# ESP-WROOM-32.net
KiCad netlist of a schematic drawn in Altium Designer
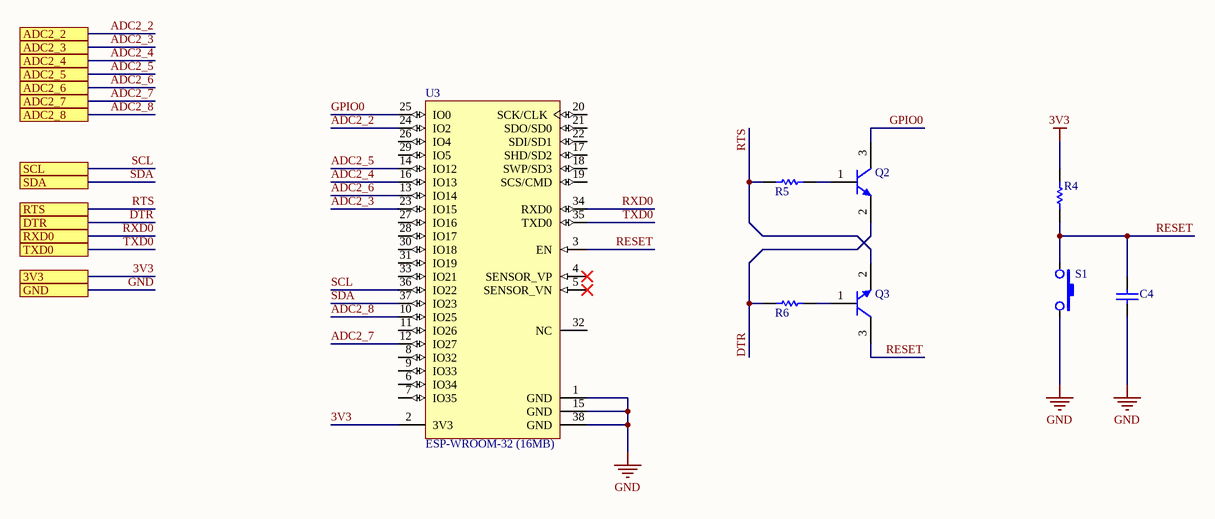
[diagram p0: ESP-WROOM-32.SchDoc]

(export (version "E")
  (design (tool "Eeschema 10.0.6"))
  (components
    (comp (ref "C4")
      (value "C0805C105K4RAC7800")
      (footprint "CAPC2013X145X50NL20T25")
      (description "1µF ±10% 16V Ceramic Capacitor X7R 0805 (2012 Metric)")
      (fields (field (name "MANUFACTURER") "Kemet"))
      (libsource (lib "Altium Content Vault") (part "CAP"))
    )
    (comp (ref "Q2")
      (value "MMBT2222ALT1G")
      (footprint "ONSC-SOT-23-3-318-08_V")
      (description "General Purpose Transistor, NPN Silicon, 3-Pin SOT-23, Pb-Free, Tape and Reel")
      (fields (field (name "MANUFACTURER") "On Semiconductor"))
      (libsource (lib "Altium Content Vault") (part "ONSC-NPN-B1E2C3-3"))
    )
    (comp (ref "Q3")
      (value "MMBT2222ALT1G")
      (footprint "ONSC-SOT-23-3-318-08_V")
      (description "General Purpose Transistor, NPN Silicon, 3-Pin SOT-23, Pb-Free, Tape and Reel")
      (fields (field (name "MANUFACTURER") "On Semiconductor"))
      (libsource (lib "Altium Content Vault") (part "ONSC-NPN-B1E2C3-3"))
    )
    (comp (ref "R4")
      (value "RK73B2ATTD103J")
      (footprint "RESC2013X60X30NL20T20")
      (fields (field (name "MANUFACTURER") "KOA Speer"))
      (libsource (lib "Altium Content Vault") (part "RES"))
    )
    (comp (ref "R5")
      (value "RK73B2ATTD103J")
      (footprint "RESC2013X60X30NL20T20")
      (fields (field (name "MANUFACTURER") "KOA Speer"))
      (libsource (lib "Altium Content Vault") (part "RES"))
    )
    (comp (ref "R6")
      (value "RK73B2ATTD103J")
      (footprint "RESC2013X60X30NL20T20")
      (fields (field (name "MANUFACTURER") "KOA Speer"))
      (libsource (lib "Altium Content Vault") (part "RES"))
    )
    (comp (ref "S1")
      (value "PTS820J25MSMTRLFS")
      (footprint "SMT_SW_PTS_820")
      (description "Tactile Switch SPST-NO Top Actuated Surface Moun")
      (libsource (lib "LIB_FIT") (part "PTS820J25MSMTRLFS"))
    )
    (comp (ref "U3")
      (value "ESP-WROOM-32 (16MB)")
      (footprint "OLMX-ESP-WROOM-32")
      (description "Espressif System, 2.7 to 3.6 V, -40 to 85 degC, 38-Pin SMD")
      (libsource (lib "Altium Content Vault") (part "OLMX-ESP-WROOM-32-38"))
    )
  )
  (nets
    (net (code "1") (name "/ADC2_2") (class "Default")
      (node (ref "U3") (pin "24") (pinfunction "IO2_24") (pintype "bidirectional"))
    )
    (net (code "2") (name "/ADC2_3") (class "Default")
      (node (ref "U3") (pin "23") (pinfunction "IO15_23") (pintype "bidirectional"))
    )
    (net (code "3") (name "/ADC2_4") (class "Default")
      (node (ref "U3") (pin "16") (pinfunction "IO13_16") (pintype "bidirectional"))
    )
    (net (code "4") (name "/ADC2_5") (class "Default")
      (node (ref "U3") (pin "14") (pinfunction "IO12_14") (pintype "bidirectional"))
    )
    (net (code "5") (name "/ADC2_6") (class "Default")
      (node (ref "U3") (pin "13") (pinfunction "IO14_13") (pintype "bidirectional"))
    )
    (net (code "6") (name "/ADC2_7") (class "Default")
      (node (ref "U3") (pin "12") (pinfunction "IO27_12") (pintype "bidirectional"))
    )
    (net (code "7") (name "/ADC2_8") (class "Default")
      (node (ref "U3") (pin "10") (pinfunction "IO25_10") (pintype "bidirectional"))
    )
    (net (code "8") (name "/DTR") (class "Default")
      (node (ref "Q2") (pin "2") (pinfunction "E_2") (pintype "passive"))
      (node (ref "R6") (pin "2") (pinfunction "2_2") (pintype "passive"))
    )
    (net (code "9") (name "/GPIO0") (class "Default")
      (node (ref "Q2") (pin "3") (pinfunction "C_3") (pintype "passive"))
      (node (ref "U3") (pin "25") (pinfunction "IO0_25") (pintype "bidirectional"))
    )
    (net (code "10") (name "/RESET") (class "Default")
      (node (ref "C4") (pin "2") (pinfunction "2_2") (pintype "passive"))
      (node (ref "Q3") (pin "3") (pinfunction "C_3") (pintype "passive"))
      (node (ref "R4") (pin "1") (pinfunction "1_1") (pintype "passive"))
      (node (ref "S1") (pin "1") (pinfunction "1_1") (pintype "passive"))
      (node (ref "U3") (pin "3") (pinfunction "EN_3") (pintype "input"))
    )
    (net (code "11") (name "/RTS") (class "Default")
      (node (ref "Q3") (pin "2") (pinfunction "E_2") (pintype "passive"))
      (node (ref "R5") (pin "2") (pinfunction "2_2") (pintype "passive"))
    )
    (net (code "12") (name "/RXD0") (class "Default")
      (node (ref "U3") (pin "34") (pinfunction "RXD0_34") (pintype "bidirectional"))
    )
    (net (code "13") (name "/SCL") (class "Default")
      (node (ref "U3") (pin "36") (pinfunction "IO22_36") (pintype "bidirectional"))
    )
    (net (code "14") (name "/SDA") (class "Default")
      (node (ref "U3") (pin "37") (pinfunction "IO23_37") (pintype "bidirectional"))
    )
    (net (code "15") (name "/TXD0") (class "Default")
      (node (ref "U3") (pin "35") (pinfunction "TXD0_35") (pintype "bidirectional"))
    )
    (net (code "16") (name "3V3") (class "Default")
      (node (ref "R4") (pin "2") (pinfunction "2_2") (pintype "passive"))
      (node (ref "U3") (pin "2") (pinfunction "3V3_2") (pintype "power_in"))
    )
    (net (code "17") (name "GND") (class "Default")
      (node (ref "C4") (pin "1") (pinfunction "1_1") (pintype "passive"))
      (node (ref "S1") (pin "2") (pinfunction "2_2") (pintype "passive"))
      (node (ref "U3") (pin "1") (pinfunction "GND_1") (pintype "power_in"))
      (node (ref "U3") (pin "15") (pinfunction "GND_15") (pintype "power_in"))
      (node (ref "U3") (pin "38") (pinfunction "GND_38") (pintype "power_in"))
    )
    (net (code "18") (name "Net-(Q2-B)") (class "Default")
      (node (ref "Q2") (pin "1") (pinfunction "B_1") (pintype "passive"))
      (node (ref "R5") (pin "1") (pinfunction "1_1") (pintype "passive"))
    )
    (net (code "19") (name "Net-(Q3-B)") (class "Default")
      (node (ref "Q3") (pin "1") (pinfunction "B_1") (pintype "passive"))
      (node (ref "R6") (pin "1") (pinfunction "1_1") (pintype "passive"))
    )
    (net (code "20") (name "unconnected-(U3-IO4-Pad26)") (class "Default")
      (node (ref "U3") (pin "26") (pinfunction "IO4_26") (pintype "bidirectional"))
    )
    (net (code "21") (name "unconnected-(U3-IO5-Pad29)") (class "Default")
      (node (ref "U3") (pin "29") (pinfunction "IO5_29") (pintype "bidirectional"))
    )
    (net (code "22") (name "unconnected-(U3-IO16-Pad27)") (class "Default")
      (node (ref "U3") (pin "27") (pinfunction "IO16_27") (pintype "bidirectional"))
    )
    (net (code "23") (name "unconnected-(U3-IO17-Pad28)") (class "Default")
      (node (ref "U3") (pin "28") (pinfunction "IO17_28") (pintype "bidirectional"))
    )
    (net (code "24") (name "unconnected-(U3-IO18-Pad30)") (class "Default")
      (node (ref "U3") (pin "30") (pinfunction "IO18_30") (pintype "bidirectional"))
    )
    (net (code "25") (name "unconnected-(U3-IO19-Pad31)") (class "Default")
      (node (ref "U3") (pin "31") (pinfunction "IO19_31") (pintype "bidirectional"))
    )
    (net (code "26") (name "unconnected-(U3-IO21-Pad33)") (class "Default")
      (node (ref "U3") (pin "33") (pinfunction "IO21_33") (pintype "bidirectional"))
    )
    (net (code "27") (name "unconnected-(U3-IO26-Pad11)") (class "Default")
      (node (ref "U3") (pin "11") (pinfunction "IO26_11") (pintype "bidirectional"))
    )
    (net (code "28") (name "unconnected-(U3-IO32-Pad8)") (class "Default")
      (node (ref "U3") (pin "8") (pinfunction "IO32_8") (pintype "bidirectional"))
    )
    (net (code "29") (name "unconnected-(U3-IO33-Pad9)") (class "Default")
      (node (ref "U3") (pin "9") (pinfunction "IO33_9") (pintype "bidirectional"))
    )
    (net (code "30") (name "unconnected-(U3-IO34-Pad6)") (class "Default")
      (node (ref "U3") (pin "6") (pinfunction "IO34_6") (pintype "bidirectional"))
    )
    (net (code "31") (name "unconnected-(U3-IO35-Pad7)") (class "Default")
      (node (ref "U3") (pin "7") (pinfunction "IO35_7") (pintype "bidirectional"))
    )
    (net (code "32") (name "unconnected-(U3-NC-Pad32)") (class "Default")
      (node (ref "U3") (pin "32") (pinfunction "NC_32") (pintype "passive"))
    )
    (net (code "33") (name "unconnected-(U3-SCK{slash}CLK-Pad20)") (class "Default")
      (node (ref "U3") (pin "20") (pinfunction "SCK/CLK_20") (pintype "bidirectional"))
    )
    (net (code "34") (name "unconnected-(U3-SCS{slash}CMD-Pad19)") (class "Default")
      (node (ref "U3") (pin "19") (pinfunction "SCS/CMD_19") (pintype "bidirectional"))
    )
    (net (code "35") (name "unconnected-(U3-SDI{slash}SD1-Pad22)") (class "Default")
      (node (ref "U3") (pin "22") (pinfunction "SDI/SD1_22") (pintype "bidirectional"))
    )
    (net (code "36") (name "unconnected-(U3-SDO{slash}SD0-Pad21)") (class "Default")
      (node (ref "U3") (pin "21") (pinfunction "SDO/SD0_21") (pintype "bidirectional"))
    )
    (net (code "37") (name "unconnected-(U3-SENSOR_VN-Pad5)") (class "Default")
      (node (ref "U3") (pin "5") (pinfunction "SENSOR_VN_5") (pintype "input+no_connect"))
    )
    (net (code "38") (name "unconnected-(U3-SENSOR_VP-Pad4)") (class "Default")
      (node (ref "U3") (pin "4") (pinfunction "SENSOR_VP_4") (pintype "input+no_connect"))
    )
    (net (code "39") (name "unconnected-(U3-SHD{slash}SD2-Pad17)") (class "Default")
      (node (ref "U3") (pin "17") (pinfunction "SHD/SD2_17") (pintype "bidirectional"))
    )
    (net (code "40") (name "unconnected-(U3-SWP{slash}SD3-Pad18)") (class "Default")
      (node (ref "U3") (pin "18") (pinfunction "SWP/SD3_18") (pintype "bidirectional"))
    )
  )
)
